# board.net
KiCad netlist of a schematic drawn in EAGLE
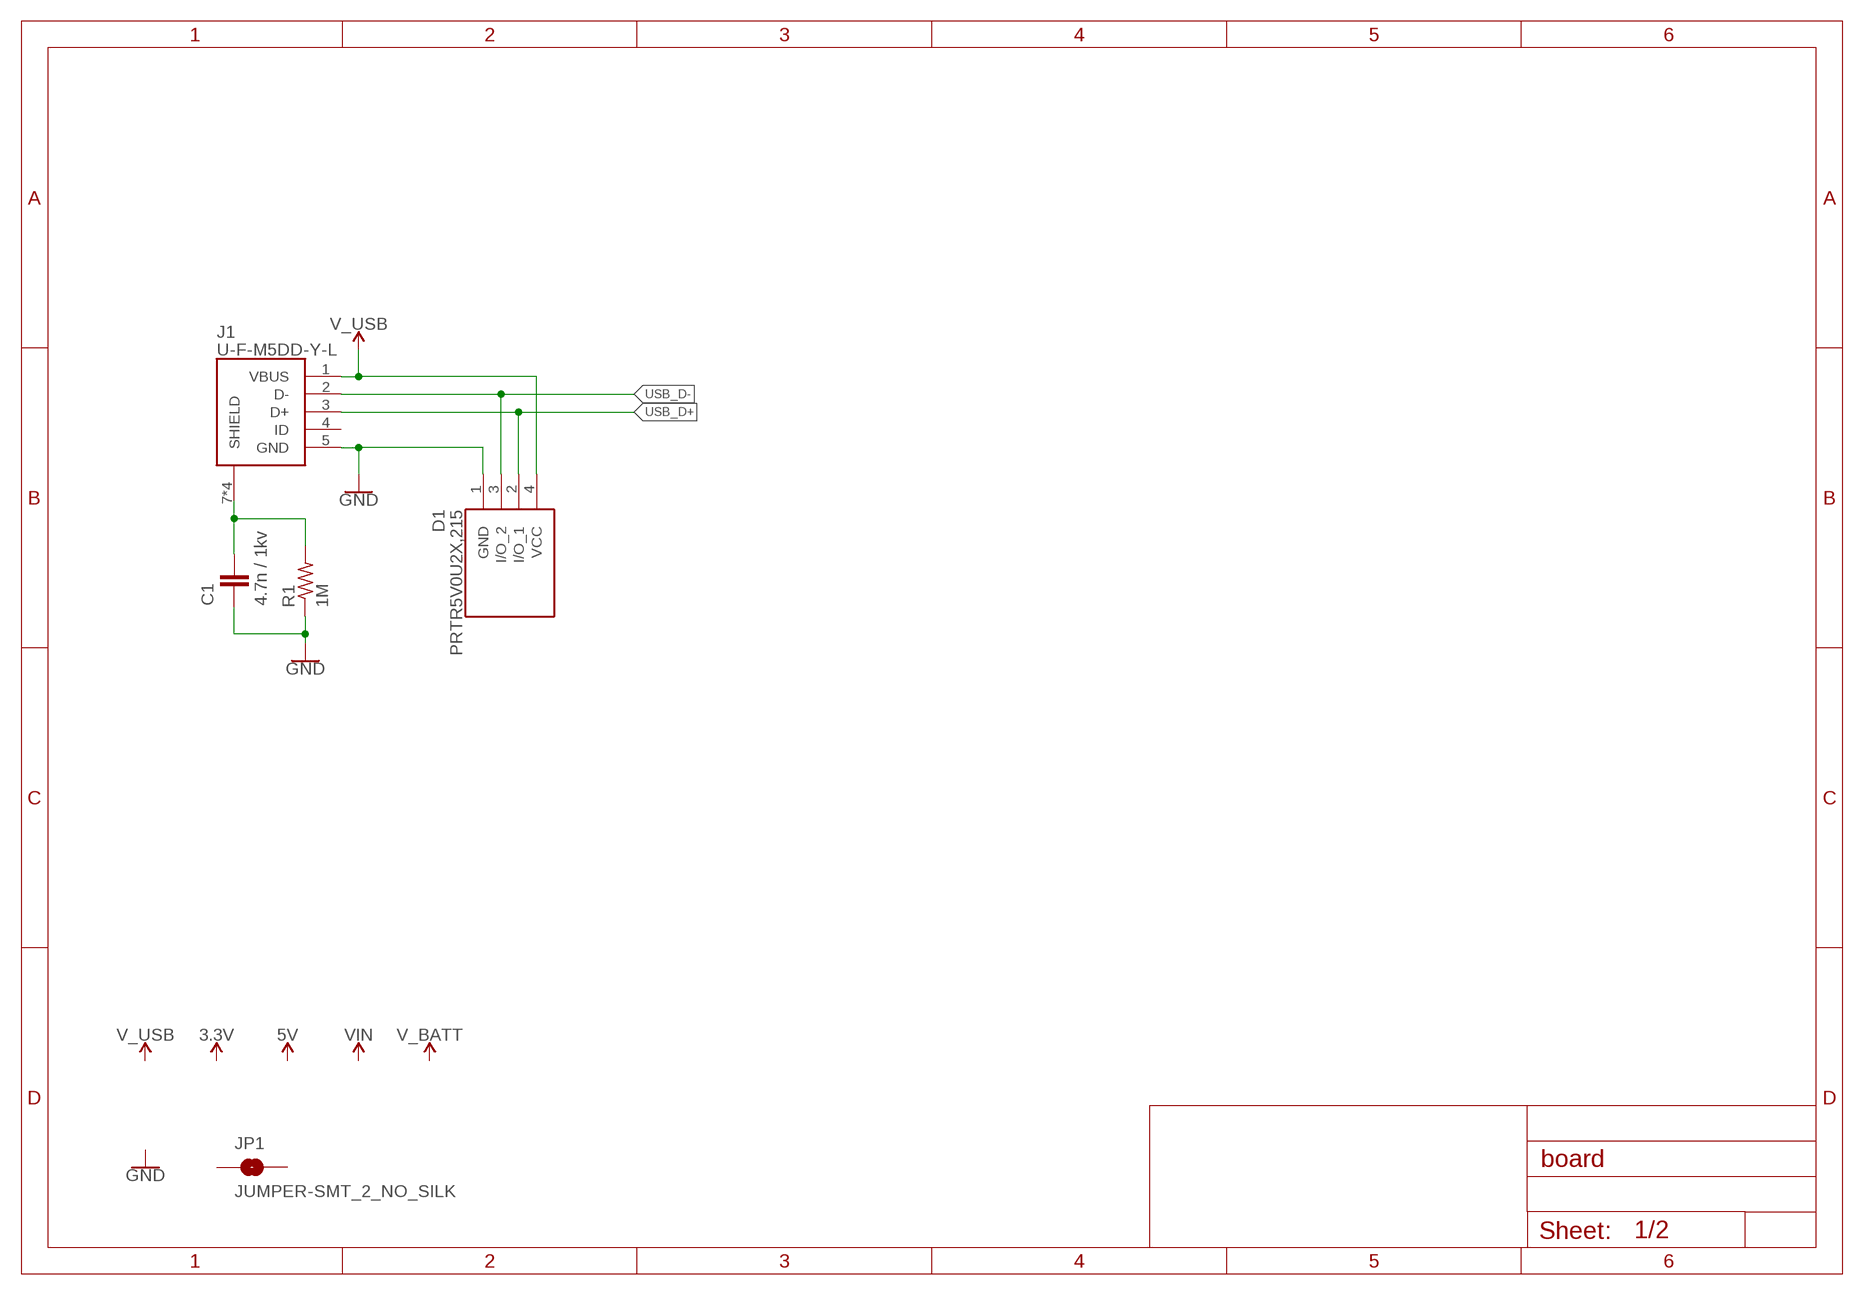
[diagram p0: schematic, sheet 1]
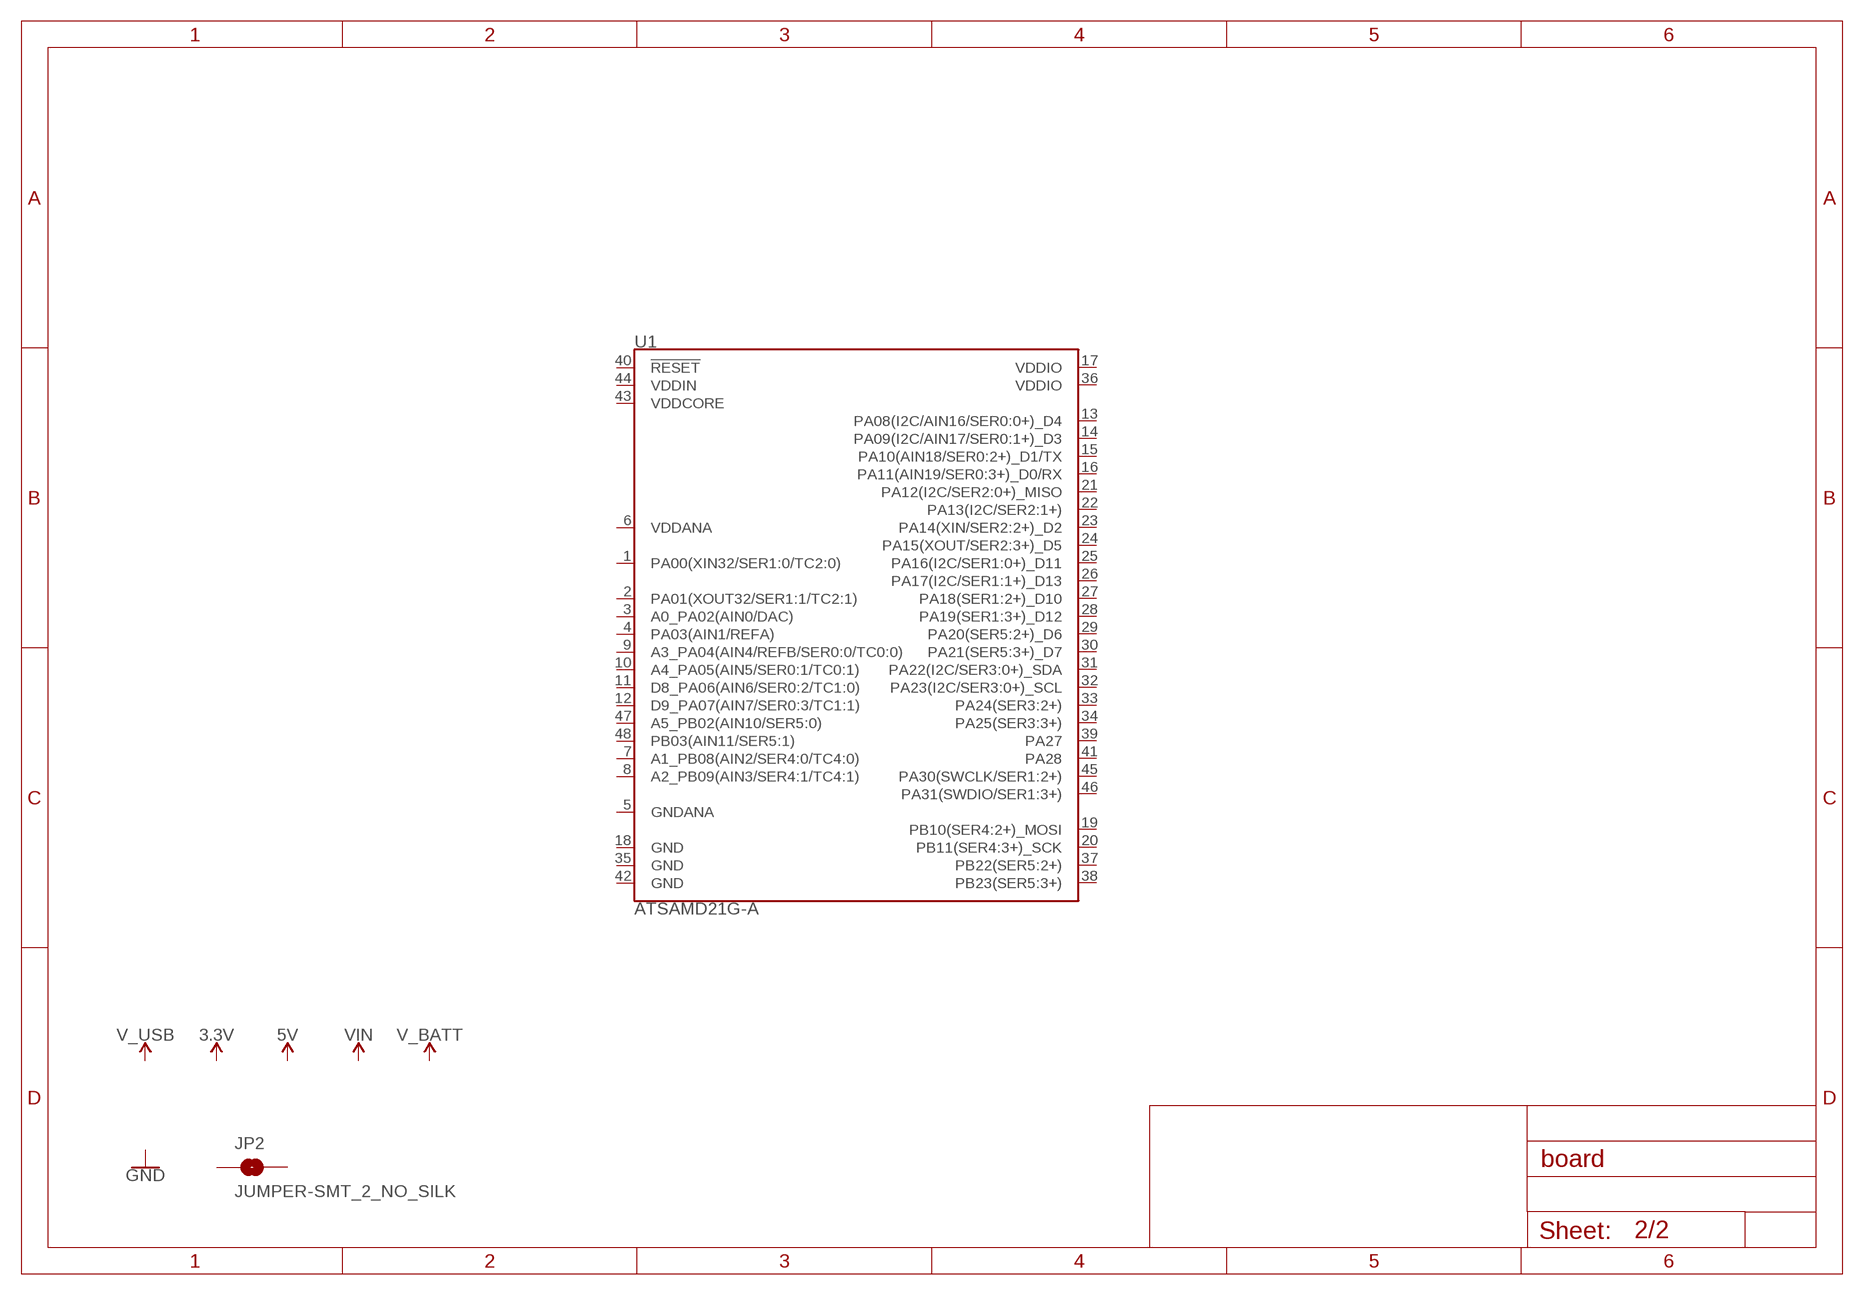
[diagram p1: schematic, sheet 2]

(export (version "E")
  (design (tool "Eeschema 10.0.6"))
  (components
    (comp (ref "JP2")
      (value "JUMPER-SMT_2_NO_SILK")
      (footprint "eagle-import:SMT-JUMPER_2_NO_SILK")
      (libsource (lib "eagle-import") (part "JUMPER-SMT_2_NO_SILK"))
    )
    (comp (ref "U1")
      (value "ATSAMD21G-A")
      (footprint "eagle-import:TQFP-48")
      (libsource (lib "eagle-import") (part "ATSAMD21G-A"))
    )
    (comp (ref "C1")
      (value "4.7n / 1kv")
      (footprint "eagle-import:C0402K")
      (libsource (lib "eagle-import") (part "C-EUC0402K"))
    )
    (comp (ref "D1")
      (value "PRTR5V0U2X,215")
      (footprint "eagle-import:SOT-143B")
      (fields (field (name "LCSC_PART_NUMBER") "C12333"))
      (libsource (lib "eagle-import") (part "PRTR5V0U2X,215"))
    )
    (comp (ref "J1")
      (value "U-F-M5DD-Y-L")
      (footprint "eagle-import:UFM5DDYL")
      (fields (field (name "LCSC_PART_NUMBER") "C91146"))
      (libsource (lib "eagle-import") (part "U-F-M5DD-Y-L"))
    )
    (comp (ref "JP1")
      (value "JUMPER-SMT_2_NO_SILK")
      (footprint "eagle-import:SMT-JUMPER_2_NO_SILK")
      (libsource (lib "eagle-import") (part "JUMPER-SMT_2_NO_SILK"))
    )
    (comp (ref "R1")
      (value "1M")
      (footprint "eagle-import:R0402")
      (libsource (lib "eagle-import") (part "R-US_R0402"))
    )
  )
  (nets
    (net (code "3") (name "GND") (class "Default")
      (node (ref "C1") (pin "2") (pinfunction "2_2") (pintype "passive"))
      (node (ref "D1") (pin "1") (pinfunction "GND_1") (pintype "power_in"))
      (node (ref "J1") (pin "5") (pinfunction "GND_5") (pintype "bidirectional"))
      (node (ref "R1") (pin "1") (pinfunction "1_1") (pintype "passive"))
    )
    (net (code "4") (name "Net-(C1-Pad1)") (class "Default")
      (node (ref "C1") (pin "1") (pinfunction "1_1") (pintype "passive"))
      (node (ref "J1") (pin "10") (pinfunction "SHIELD_10") (pintype "bidirectional"))
      (node (ref "J1") (pin "7") (pinfunction "SHIELD_7") (pintype "bidirectional"))
      (node (ref "J1") (pin "8") (pinfunction "SHIELD_8") (pintype "bidirectional"))
      (node (ref "J1") (pin "9") (pinfunction "SHIELD_9") (pintype "bidirectional"))
      (node (ref "R1") (pin "2") (pinfunction "2_2") (pintype "passive"))
    )
    (net (code "5") (name "USB_D+") (class "Default")
      (node (ref "D1") (pin "2") (pinfunction "I/O_1_2") (pintype "bidirectional"))
      (node (ref "J1") (pin "3") (pinfunction "D+_3") (pintype "bidirectional"))
    )
    (net (code "6") (name "USB_D-") (class "Default")
      (node (ref "D1") (pin "3") (pinfunction "I/O_2_3") (pintype "bidirectional"))
      (node (ref "J1") (pin "2") (pinfunction "D-_2") (pintype "bidirectional"))
    )
    (net (code "9") (name "V_USB") (class "Default")
      (node (ref "D1") (pin "4") (pinfunction "VCC_4") (pintype "power_in"))
      (node (ref "J1") (pin "1") (pinfunction "VBUS_1") (pintype "bidirectional"))
    )
    (net (code "10") (name "unconnected-(J1-ID-Pad4)") (class "Default")
      (node (ref "J1") (pin "4") (pinfunction "ID_4") (pintype "bidirectional"))
    )
    (net (code "11") (name "unconnected-(JP1-Pad1)") (class "Default")
      (node (ref "JP1") (pin "1") (pinfunction "1_1") (pintype "passive"))
    )
    (net (code "12") (name "unconnected-(JP1-Pad2)") (class "Default")
      (node (ref "JP1") (pin "2") (pinfunction "2_2") (pintype "passive"))
    )
    (net (code "13") (name "unconnected-(JP2-Pad1)") (class "Default")
      (node (ref "JP2") (pin "1") (pinfunction "1_1") (pintype "passive"))
    )
    (net (code "14") (name "unconnected-(JP2-Pad2)") (class "Default")
      (node (ref "JP2") (pin "2") (pinfunction "2_2") (pintype "passive"))
    )
    (net (code "15") (name "unconnected-(U1-A0_PA02(AIN0{slash}DAC)-Pad3)") (class "Default")
      (node (ref "U1") (pin "3") (pinfunction "A0_PA02(AIN0/DAC)_3") (pintype "bidirectional"))
    )
    (net (code "16") (name "unconnected-(U1-A1_PB08(AIN2{slash}SER4:0{slash}TC4:0)-Pad7)") (class "Default")
      (node (ref "U1") (pin "7") (pinfunction "A1_PB08(AIN2/SER4:0/TC4:0)_7") (pintype "bidirectional"))
    )
    (net (code "17") (name "unconnected-(U1-A2_PB09(AIN3{slash}SER4:1{slash}TC4:1)-Pad8)") (class "Default")
      (node (ref "U1") (pin "8") (pinfunction "A2_PB09(AIN3/SER4:1/TC4:1)_8") (pintype "bidirectional"))
    )
    (net (code "18") (name "unconnected-(U1-A3_PA04(AIN4{slash}REFB{slash}SER0:0{slash}TC0:0)-Pad9)") (class "Default")
      (node (ref "U1") (pin "9") (pinfunction "A3_PA04(AIN4/REFB/SER0:0/TC0:0)_9") (pintype "bidirectional"))
    )
    (net (code "19") (name "unconnected-(U1-A4_PA05(AIN5{slash}SER0:1{slash}TC0:1)-Pad10)") (class "Default")
      (node (ref "U1") (pin "10") (pinfunction "A4_PA05(AIN5/SER0:1/TC0:1)_10") (pintype "bidirectional"))
    )
    (net (code "20") (name "unconnected-(U1-A5_PB02(AIN10{slash}SER5:0)-Pad47)") (class "Default")
      (node (ref "U1") (pin "47") (pinfunction "A5_PB02(AIN10/SER5:0)_47") (pintype "bidirectional"))
    )
    (net (code "21") (name "unconnected-(U1-D8_PA06(AIN6{slash}SER0:2{slash}TC1:0)-Pad11)") (class "Default")
      (node (ref "U1") (pin "11") (pinfunction "D8_PA06(AIN6/SER0:2/TC1:0)_11") (pintype "bidirectional"))
    )
    (net (code "22") (name "unconnected-(U1-D9_PA07(AIN7{slash}SER0:3{slash}TC1:1)-Pad12)") (class "Default")
      (node (ref "U1") (pin "12") (pinfunction "D9_PA07(AIN7/SER0:3/TC1:1)_12") (pintype "bidirectional"))
    )
    (net (code "23") (name "unconnected-(U1-GND-Pad18)") (class "Default")
      (node (ref "U1") (pin "18") (pinfunction "GND_18") (pintype "bidirectional"))
    )
    (net (code "24") (name "unconnected-(U1-GND-Pad35)") (class "Default")
      (node (ref "U1") (pin "35") (pinfunction "GND_35") (pintype "bidirectional"))
    )
    (net (code "25") (name "unconnected-(U1-GND-Pad42)") (class "Default")
      (node (ref "U1") (pin "42") (pinfunction "GND_42") (pintype "bidirectional"))
    )
    (net (code "26") (name "unconnected-(U1-GNDANA-Pad5)") (class "Default")
      (node (ref "U1") (pin "5") (pinfunction "GNDANA_5") (pintype "bidirectional"))
    )
    (net (code "27") (name "unconnected-(U1-PA00(XIN32{slash}SER1:0{slash}TC2:0)-Pad1)") (class "Default")
      (node (ref "U1") (pin "1") (pinfunction "PA00(XIN32/SER1:0/TC2:0)_1") (pintype "bidirectional"))
    )
    (net (code "28") (name "unconnected-(U1-PA01(XOUT32{slash}SER1:1{slash}TC2:1)-Pad2)") (class "Default")
      (node (ref "U1") (pin "2") (pinfunction "PA01(XOUT32/SER1:1/TC2:1)_2") (pintype "bidirectional"))
    )
    (net (code "29") (name "unconnected-(U1-PA03(AIN1{slash}REFA)-Pad4)") (class "Default")
      (node (ref "U1") (pin "4") (pinfunction "PA03(AIN1/REFA)_4") (pintype "bidirectional"))
    )
    (net (code "30") (name "unconnected-(U1-PA08(I2C{slash}AIN16{slash}SER0:0+)_D4-Pad13)") (class "Default")
      (node (ref "U1") (pin "13") (pinfunction "PA08(I2C/AIN16/SER0:0+)_D4_13") (pintype "bidirectional"))
    )
    (net (code "31") (name "unconnected-(U1-PA09(I2C{slash}AIN17{slash}SER0:1+)_D3-Pad14)") (class "Default")
      (node (ref "U1") (pin "14") (pinfunction "PA09(I2C/AIN17/SER0:1+)_D3_14") (pintype "bidirectional"))
    )
    (net (code "32") (name "unconnected-(U1-PA10(AIN18{slash}SER0:2+)_D1{slash}TX-Pad15)") (class "Default")
      (node (ref "U1") (pin "15") (pinfunction "PA10(AIN18/SER0:2+)_D1/TX_15") (pintype "bidirectional"))
    )
    (net (code "33") (name "unconnected-(U1-PA11(AIN19{slash}SER0:3+)_D0{slash}RX-Pad16)") (class "Default")
      (node (ref "U1") (pin "16") (pinfunction "PA11(AIN19/SER0:3+)_D0/RX_16") (pintype "bidirectional"))
    )
    (net (code "34") (name "unconnected-(U1-PA12(I2C{slash}SER2:0+)_MISO-Pad21)") (class "Default")
      (node (ref "U1") (pin "21") (pinfunction "PA12(I2C/SER2:0+)_MISO_21") (pintype "bidirectional"))
    )
    (net (code "35") (name "unconnected-(U1-PA13(I2C{slash}SER2:1+)-Pad22)") (class "Default")
      (node (ref "U1") (pin "22") (pinfunction "PA13(I2C/SER2:1+)_22") (pintype "bidirectional"))
    )
    (net (code "36") (name "unconnected-(U1-PA14(XIN{slash}SER2:2+)_D2-Pad23)") (class "Default")
      (node (ref "U1") (pin "23") (pinfunction "PA14(XIN/SER2:2+)_D2_23") (pintype "bidirectional"))
    )
    (net (code "37") (name "unconnected-(U1-PA15(XOUT{slash}SER2:3+)_D5-Pad24)") (class "Default")
      (node (ref "U1") (pin "24") (pinfunction "PA15(XOUT/SER2:3+)_D5_24") (pintype "bidirectional"))
    )
    (net (code "38") (name "unconnected-(U1-PA16(I2C{slash}SER1:0+)_D11-Pad25)") (class "Default")
      (node (ref "U1") (pin "25") (pinfunction "PA16(I2C/SER1:0+)_D11_25") (pintype "bidirectional"))
    )
    (net (code "39") (name "unconnected-(U1-PA17(I2C{slash}SER1:1+)_D13-Pad26)") (class "Default")
      (node (ref "U1") (pin "26") (pinfunction "PA17(I2C/SER1:1+)_D13_26") (pintype "bidirectional"))
    )
    (net (code "40") (name "unconnected-(U1-PA18(SER1:2+)_D10-Pad27)") (class "Default")
      (node (ref "U1") (pin "27") (pinfunction "PA18(SER1:2+)_D10_27") (pintype "bidirectional"))
    )
    (net (code "41") (name "unconnected-(U1-PA19(SER1:3+)_D12-Pad28)") (class "Default")
      (node (ref "U1") (pin "28") (pinfunction "PA19(SER1:3+)_D12_28") (pintype "bidirectional"))
    )
    (net (code "42") (name "unconnected-(U1-PA20(SER5:2+)_D6-Pad29)") (class "Default")
      (node (ref "U1") (pin "29") (pinfunction "PA20(SER5:2+)_D6_29") (pintype "bidirectional"))
    )
    (net (code "43") (name "unconnected-(U1-PA21(SER5:3+)_D7-Pad30)") (class "Default")
      (node (ref "U1") (pin "30") (pinfunction "PA21(SER5:3+)_D7_30") (pintype "bidirectional"))
    )
    (net (code "44") (name "unconnected-(U1-PA22(I2C{slash}SER3:0+)_SDA-Pad31)") (class "Default")
      (node (ref "U1") (pin "31") (pinfunction "PA22(I2C/SER3:0+)_SDA_31") (pintype "bidirectional"))
    )
    (net (code "45") (name "unconnected-(U1-PA23(I2C{slash}SER3:0+)_SCL-Pad32)") (class "Default")
      (node (ref "U1") (pin "32") (pinfunction "PA23(I2C/SER3:0+)_SCL_32") (pintype "bidirectional"))
    )
    (net (code "46") (name "unconnected-(U1-PA24(SER3:2+)-Pad33)") (class "Default")
      (node (ref "U1") (pin "33") (pinfunction "PA24(SER3:2+)_33") (pintype "bidirectional"))
    )
    (net (code "47") (name "unconnected-(U1-PA25(SER3:3+)-Pad34)") (class "Default")
      (node (ref "U1") (pin "34") (pinfunction "PA25(SER3:3+)_34") (pintype "bidirectional"))
    )
    (net (code "48") (name "unconnected-(U1-PA27-Pad39)") (class "Default")
      (node (ref "U1") (pin "39") (pinfunction "PA27_39") (pintype "bidirectional"))
    )
    (net (code "49") (name "unconnected-(U1-PA28-Pad41)") (class "Default")
      (node (ref "U1") (pin "41") (pinfunction "PA28_41") (pintype "bidirectional"))
    )
    (net (code "50") (name "unconnected-(U1-PA30(SWCLK{slash}SER1:2+)-Pad45)") (class "Default")
      (node (ref "U1") (pin "45") (pinfunction "PA30(SWCLK/SER1:2+)_45") (pintype "bidirectional"))
    )
    (net (code "51") (name "unconnected-(U1-PA31(SWDIO{slash}SER1:3+)-Pad46)") (class "Default")
      (node (ref "U1") (pin "46") (pinfunction "PA31(SWDIO/SER1:3+)_46") (pintype "bidirectional"))
    )
    (net (code "52") (name "unconnected-(U1-PB03(AIN11{slash}SER5:1)-Pad48)") (class "Default")
      (node (ref "U1") (pin "48") (pinfunction "PB03(AIN11/SER5:1)_48") (pintype "bidirectional"))
    )
    (net (code "53") (name "unconnected-(U1-PB10(SER4:2+)_MOSI-Pad19)") (class "Default")
      (node (ref "U1") (pin "19") (pinfunction "PB10(SER4:2+)_MOSI_19") (pintype "bidirectional"))
    )
    (net (code "54") (name "unconnected-(U1-PB11(SER4:3+)_SCK-Pad20)") (class "Default")
      (node (ref "U1") (pin "20") (pinfunction "PB11(SER4:3+)_SCK_20") (pintype "bidirectional"))
    )
    (net (code "55") (name "unconnected-(U1-PB22(SER5:2+)-Pad37)") (class "Default")
      (node (ref "U1") (pin "37") (pinfunction "PB22(SER5:2+)_37") (pintype "bidirectional"))
    )
    (net (code "56") (name "unconnected-(U1-PB23(SER5:3+)-Pad38)") (class "Default")
      (node (ref "U1") (pin "38") (pinfunction "PB23(SER5:3+)_38") (pintype "bidirectional"))
    )
    (net (code "57") (name "unconnected-(U1-VDDANA-Pad6)") (class "Default")
      (node (ref "U1") (pin "6") (pinfunction "VDDANA_6") (pintype "bidirectional"))
    )
    (net (code "58") (name "unconnected-(U1-VDDCORE-Pad43)") (class "Default")
      (node (ref "U1") (pin "43") (pinfunction "VDDCORE_43") (pintype "bidirectional"))
    )
    (net (code "59") (name "unconnected-(U1-VDDIN-Pad44)") (class "Default")
      (node (ref "U1") (pin "44") (pinfunction "VDDIN_44") (pintype "bidirectional"))
    )
    (net (code "60") (name "unconnected-(U1-VDDIO-Pad17)") (class "Default")
      (node (ref "U1") (pin "17") (pinfunction "VDDIO_17") (pintype "bidirectional"))
    )
    (net (code "61") (name "unconnected-(U1-VDDIO-Pad36)") (class "Default")
      (node (ref "U1") (pin "36") (pinfunction "VDDIO_36") (pintype "bidirectional"))
    )
    (net (code "62") (name "unconnected-(U1-~{RESET}-Pad40)") (class "Default")
      (node (ref "U1") (pin "40") (pinfunction "~{RESET}_40") (pintype "bidirectional"))
    )
  )
)
